# SV601121A.net
KiCad netlist of a schematic drawn in Altium Designer
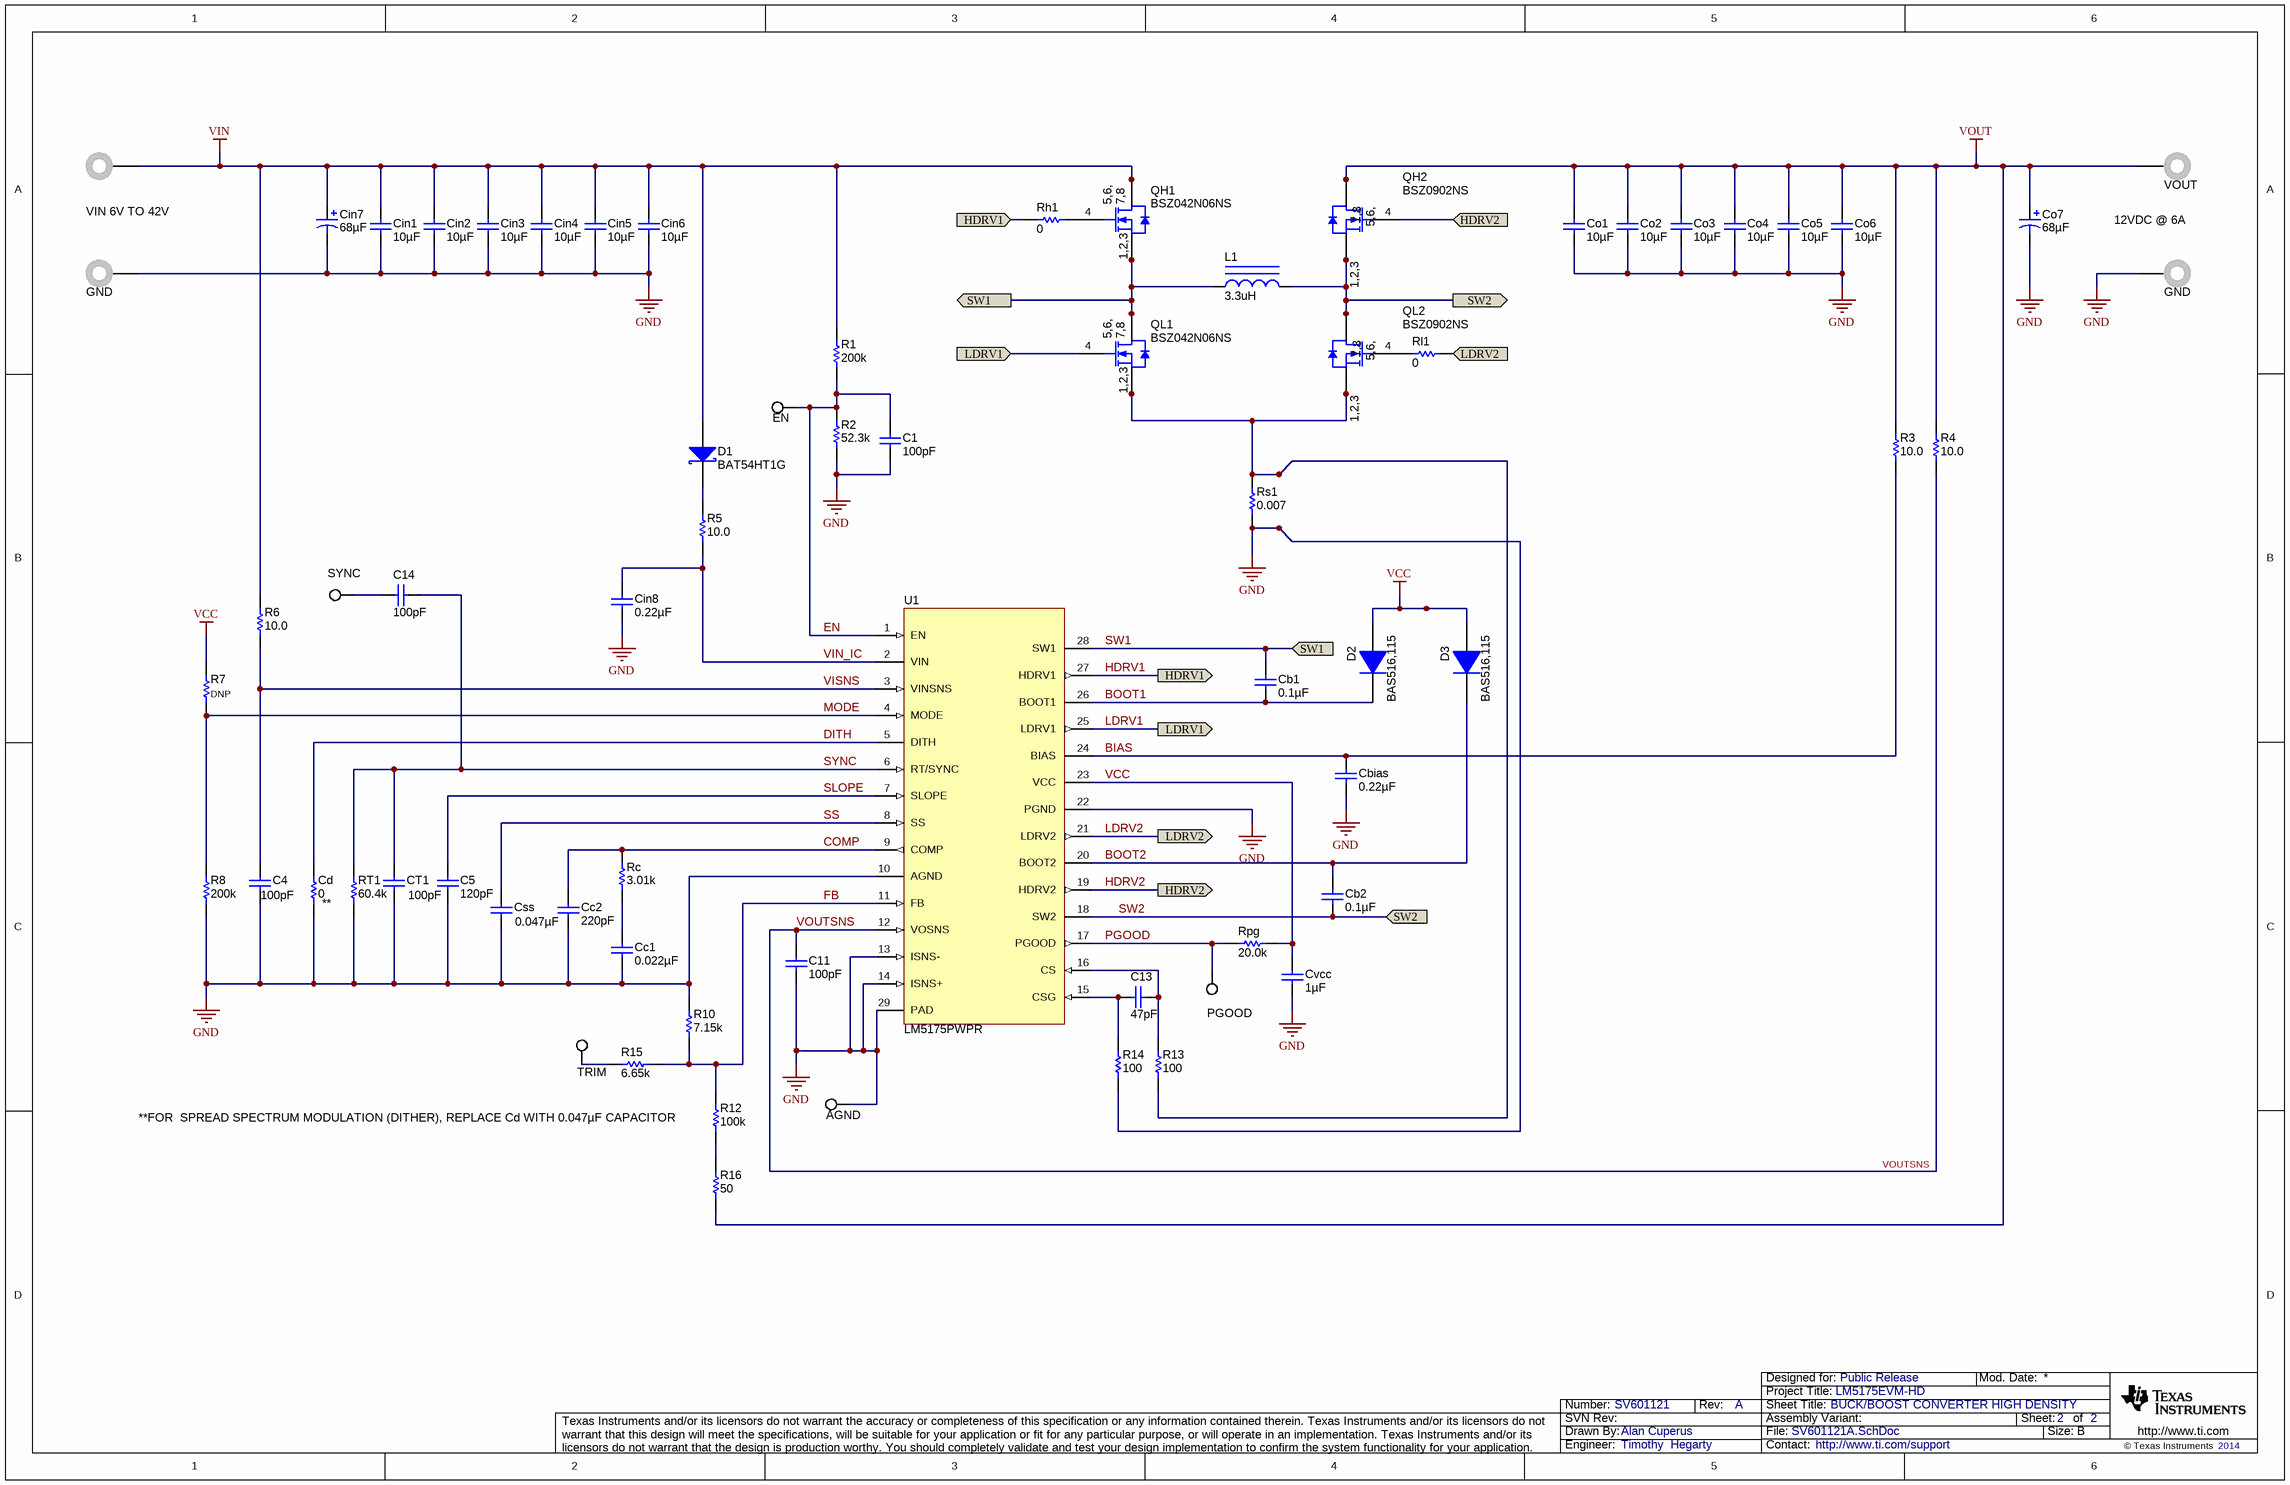
[diagram p0: SV601121A.SchDoc]

(export (version "E")
  (design (tool "Eeschema 10.0.6"))
  (components
    (comp (ref "AGND")
      (value "5015")
      (footprint "Testpoint_Keystone_Miniature")
      (description "Test Point, Miniature, SMT")
      (fields (field (name "MANUFACTURER") "Keystone") (field (name "PUBLISHER") "Texas Instruments"))
      (libsource (lib "Connectors_Keystone") (part "5015"))
    )
    (comp (ref "C1")
      (value "GRM1885C1H101JA01D")
      (footprint "0603L")
      (description "CAP, CERM, 100pF, 50V, +/-5%, C0G/NP0, 0603")
      (fields
        (field (name "VALUEDISPLAYED") "100pF")
        (field (name "MANUFACTURER") "MuRata")
        (field (name "PUBLISHER") "Texas Instruments")
      )
      (libsource (lib "Capacitor_Ceramic") (part "GRM1885C1H101JA01D"))
    )
    (comp (ref "C4")
      (value "GRM1885C1H101JA01D")
      (footprint "0603L")
      (description "CAP, CERM, 100pF, 50V, +/-5%, C0G/NP0, 0603")
      (fields
        (field (name "VALUEDISPLAYED") "100pF")
        (field (name "MANUFACTURER") "MuRata")
        (field (name "PUBLISHER") "Texas Instruments")
      )
      (libsource (lib "Capacitor_Ceramic") (part "GRM1885C1H101JA01D"))
    )
    (comp (ref "C5")
      (value "GRM1885C1H121JA01D")
      (footprint "0603L")
      (description "CAP, CERM, 120pF, 50V, +/-5%, C0G/NP0, 0603")
      (fields
        (field (name "VALUEDISPLAYED") "120pF")
        (field (name "MANUFACTURER") "MuRata")
        (field (name "PUBLISHER") "Texas Instruments")
      )
      (libsource (lib "Capacitor_Ceramic") (part "GRM1885C1H121JA01D"))
    )
    (comp (ref "C11")
      (value "GRM1885C1H101JA01D")
      (footprint "0603L")
      (description "CAP, CERM, 100pF, 50V, +/-5%, C0G/NP0, 0603")
      (fields
        (field (name "VALUEDISPLAYED") "100pF")
        (field (name "MANUFACTURER") "MuRata")
        (field (name "PUBLISHER") "Texas Instruments")
      )
      (libsource (lib "Capacitor_Ceramic") (part "GRM1885C1H101JA01D"))
    )
    (comp (ref "C13")
      (value "GRM1885C1H470JA01D")
      (footprint "0603L")
      (description "CAP, CERM, 47pF, 50V, +/-5%, C0G/NP0, 0603")
      (fields
        (field (name "VALUEDISPLAYED") "47pF")
        (field (name "MANUFACTURER") "MuRata")
        (field (name "PUBLISHER") "Texas Instruments")
      )
      (libsource (lib "Capacitor_Ceramic") (part "GRM1885C1H470JA01D"))
    )
    (comp (ref "C14")
      (value "CGA3E2NP01H101J080AA")
      (footprint "0603L")
      (description "CAP, CERM, 100pF, 50V, +/-5%, C0G/NP0, 0603")
      (fields
        (field (name "VALUEDISPLAYED") "100pF")
        (field (name "MANUFACTURER") "TDK")
        (field (name "PUBLISHER") "Texas Instruments")
      )
      (libsource (lib "Capacitor_Ceramic") (part "CGA3E2NP01H101J080AA"))
    )
    (comp (ref "Cb1")
      (value "GCM188R71H104KA57D")
      (footprint "0603L")
      (description "CAP, CERM, 0.1uF, 50V, +/-10%, X7R, 0603")
      (fields
        (field (name "VALUEDISPLAYED") "0.1µF")
        (field (name "MANUFACTURER") "MuRata")
        (field (name "PUBLISHER") "Texas Instruments")
      )
      (libsource (lib "Capacitor_Ceramic") (part "GCM188R71H104KA57D"))
    )
    (comp (ref "Cb2")
      (value "GCM188R71H104KA57D")
      (footprint "0603L")
      (description "CAP, CERM, 0.1uF, 50V, +/-10%, X7R, 0603")
      (fields
        (field (name "VALUEDISPLAYED") "0.1µF")
        (field (name "MANUFACTURER") "MuRata")
        (field (name "PUBLISHER") "Texas Instruments")
      )
      (libsource (lib "Capacitor_Ceramic") (part "GCM188R71H104KA57D"))
    )
    (comp (ref "Cbias")
      (value "C1608X7R1H224K080AB")
      (footprint "0603_HV")
      (description "CAP, CERM, 0.22uF, 50V, +/-10%, X7R, 0603")
      (fields
        (field (name "VALUEDISPLAYED") "0.22µF")
        (field (name "MANUFACTURER") "TDK")
        (field (name "PUBLISHER") "Texas Instruments")
      )
      (libsource (lib "Capacitor_Ceramic") (part "C1608X7R1H224K080AB"))
    )
    (comp (ref "Cc1")
      (value "GRM188R71H223KA01D")
      (footprint "0603L")
      (description "CAP, CERM, 0.022 µF, 50 V, +/- 10%, X7R, 0603")
      (fields
        (field (name "VALUEDISPLAYED") "0.022µF")
        (field (name "MANUFACTURER") "MuRata")
        (field (name "PUBLISHER") "Texas Instruments")
      )
      (libsource (lib "Capacitor_Ceramic") (part "GRM188R71H223KA01D"))
    )
    (comp (ref "Cc2")
      (value "GRM1885C1H221JA01D")
      (footprint "0603L")
      (description "CAP, CERM, 220 pF, 50 V, +/- 5%, C0G/NP0, 0603")
      (fields
        (field (name "VALUEDISPLAYED") "220pF")
        (field (name "MANUFACTURER") "MuRata")
        (field (name "PUBLISHER") "Texas Instruments")
      )
      (libsource (lib "Capacitor_Ceramic") (part "GRM1885C1H221JA01D"))
    )
    (comp (ref "Cd")
      (value "RC0603JR-070RL")
      (footprint "0603L")
      (description "RES, 0, 5%, 0.1 W, 0603")
      (fields
        (field (name "MANUFACTURER") "Yageo America")
        (field (name "VALUEDISPLAYED") "0")
        (field (name "PUBLISHER") "Texas Instruments")
      )
      (libsource (lib "Resistor_0603") (part "RC0603JR-070RL"))
    )
    (comp (ref "Cin1")
      (value "GRM32ER71H106KA12L")
      (footprint "1210L")
      (description "CAP, CERM, 10uF, 50V, +/-10%, X7R, 1210")
      (fields
        (field (name "VALUEDISPLAYED") "10µF")
        (field (name "MANUFACTURER") "MuRata")
        (field (name "PUBLISHER") "Texas Instruments")
      )
      (libsource (lib "Capacitor_Ceramic") (part "GRM32ER71H106KA12L"))
    )
    (comp (ref "Cin2")
      (value "GRM32ER71H106KA12L")
      (footprint "1210L")
      (description "CAP, CERM, 10uF, 50V, +/-10%, X7R, 1210")
      (fields
        (field (name "VALUEDISPLAYED") "10µF")
        (field (name "MANUFACTURER") "MuRata")
        (field (name "PUBLISHER") "Texas Instruments")
      )
      (libsource (lib "Capacitor_Ceramic") (part "GRM32ER71H106KA12L"))
    )
    (comp (ref "Cin3")
      (value "GRM32ER71H106KA12L")
      (footprint "1210L")
      (description "CAP, CERM, 10uF, 50V, +/-10%, X7R, 1210")
      (fields
        (field (name "VALUEDISPLAYED") "10µF")
        (field (name "MANUFACTURER") "MuRata")
        (field (name "PUBLISHER") "Texas Instruments")
      )
      (libsource (lib "Capacitor_Ceramic") (part "GRM32ER71H106KA12L"))
    )
    (comp (ref "Cin4")
      (value "GRM32ER71H106KA12L")
      (footprint "1210L")
      (description "CAP, CERM, 10uF, 50V, +/-10%, X7R, 1210")
      (fields
        (field (name "VALUEDISPLAYED") "10µF")
        (field (name "MANUFACTURER") "MuRata")
        (field (name "PUBLISHER") "Texas Instruments")
      )
      (libsource (lib "Capacitor_Ceramic") (part "GRM32ER71H106KA12L"))
    )
    (comp (ref "Cin5")
      (value "GRM32ER71H106KA12L")
      (footprint "1210L")
      (description "CAP, CERM, 10uF, 50V, +/-10%, X7R, 1210")
      (fields
        (field (name "VALUEDISPLAYED") "10µF")
        (field (name "MANUFACTURER") "MuRata")
        (field (name "PUBLISHER") "Texas Instruments")
      )
      (libsource (lib "Capacitor_Ceramic") (part "GRM32ER71H106KA12L"))
    )
    (comp (ref "Cin6")
      (value "GRM32ER71H106KA12L")
      (footprint "1210L")
      (description "CAP, CERM, 10uF, 50V, +/-10%, X7R, 1210")
      (fields
        (field (name "VALUEDISPLAYED") "10µF")
        (field (name "MANUFACTURER") "MuRata")
        (field (name "PUBLISHER") "Texas Instruments")
      )
      (libsource (lib "Capacitor_Ceramic") (part "GRM32ER71H106KA12L"))
    )
    (comp (ref "Cin7")
      (value "EEHZC1H680P")
      (footprint "SM_RADIAL_8MM")
      (description "CAP, AL, 68 µF, 50 V, +/- 20%, 30 ohm, SMD")
      (fields
        (field (name "VALUEDISPLAYED") "68µF")
        (field (name "MANUFACTURER") "Panasonic")
        (field (name "PUBLISHER") "Texas Instruments")
      )
      (libsource (lib "Capacitor_Aluminum") (part "EEHZC1H680P"))
    )
    (comp (ref "Cin8")
      (value "C1608X7R1H224K080AB")
      (footprint "0603_HV")
      (description "CAP, CERM, 0.22uF, 50V, +/-10%, X7R, 0603")
      (fields
        (field (name "VALUEDISPLAYED") "0.22µF")
        (field (name "MANUFACTURER") "TDK")
        (field (name "PUBLISHER") "Texas Instruments")
      )
      (libsource (lib "Capacitor_Ceramic") (part "C1608X7R1H224K080AB"))
    )
    (comp (ref "Co1")
      (value "GRM32ER71H106KA12L")
      (footprint "1210L")
      (description "CAP, CERM, 10 µF, 50 V, +/- 10%, X7R, 1210")
      (fields
        (field (name "VALUEDISPLAYED") "10µF")
        (field (name "MANUFACTURER") "MuRata")
        (field (name "PUBLISHER") "Texas Instruments")
      )
      (libsource (lib "Capacitor_Ceramic") (part "GRM32ER71H106KA12L"))
    )
    (comp (ref "Co2")
      (value "GRM32ER71H106KA12L")
      (footprint "1210L")
      (description "CAP, CERM, 10 µF, 50 V, +/- 10%, X7R, 1210")
      (fields
        (field (name "VALUEDISPLAYED") "10µF")
        (field (name "MANUFACTURER") "MuRata")
        (field (name "PUBLISHER") "Texas Instruments")
      )
      (libsource (lib "Capacitor_Ceramic") (part "GRM32ER71H106KA12L"))
    )
    (comp (ref "Co3")
      (value "GRM32ER71H106KA12L")
      (footprint "1210L")
      (description "CAP, CERM, 10 µF, 50 V, +/- 10%, X7R, 1210")
      (fields
        (field (name "VALUEDISPLAYED") "10µF")
        (field (name "MANUFACTURER") "MuRata")
        (field (name "PUBLISHER") "Texas Instruments")
      )
      (libsource (lib "Capacitor_Ceramic") (part "GRM32ER71H106KA12L"))
    )
    (comp (ref "Co4")
      (value "GRM32ER71H106KA12L")
      (footprint "1210L")
      (description "CAP, CERM, 10 µF, 50 V, +/- 10%, X7R, 1210")
      (fields
        (field (name "VALUEDISPLAYED") "10µF")
        (field (name "MANUFACTURER") "MuRata")
        (field (name "PUBLISHER") "Texas Instruments")
      )
      (libsource (lib "Capacitor_Ceramic") (part "GRM32ER71H106KA12L"))
    )
    (comp (ref "Co5")
      (value "GRM32ER71H106KA12L")
      (footprint "1210L")
      (description "CAP, CERM, 10 µF, 50 V, +/- 10%, X7R, 1210")
      (fields
        (field (name "VALUEDISPLAYED") "10µF")
        (field (name "MANUFACTURER") "MuRata")
        (field (name "PUBLISHER") "Texas Instruments")
      )
      (libsource (lib "Capacitor_Ceramic") (part "GRM32ER71H106KA12L"))
    )
    (comp (ref "Co6")
      (value "GRM32ER71H106KA12L")
      (footprint "1210L")
      (description "CAP, CERM, 10 µF, 50 V, +/- 10%, X7R, 1210")
      (fields
        (field (name "VALUEDISPLAYED") "10µF")
        (field (name "MANUFACTURER") "MuRata")
        (field (name "PUBLISHER") "Texas Instruments")
      )
      (libsource (lib "Capacitor_Ceramic") (part "GRM32ER71H106KA12L"))
    )
    (comp (ref "Co7")
      (value "EEHZC1H680P")
      (footprint "SM_RADIAL_8MM")
      (description "CAP, AL, 68 µF, 50 V, +/- 20%, 30 ohm, SMD")
      (fields
        (field (name "VALUEDISPLAYED") "68µF")
        (field (name "MANUFACTURER") "Panasonic")
        (field (name "PUBLISHER") "Texas Instruments")
      )
      (libsource (lib "Capacitor_Aluminum") (part "EEHZC1H680P"))
    )
    (comp (ref "Css")
      (value "GRM188R71H473KA61D")
      (footprint "0603L")
      (description "CAP, CERM, 0.047 µF, 50 V, +/- 10%, X7R, 0603")
      (fields
        (field (name "VALUEDISPLAYED") "0.047µF")
        (field (name "MANUFACTURER") "MuRata")
        (field (name "PUBLISHER") "Texas Instruments")
      )
      (libsource (lib "Capacitor_Ceramic") (part "GRM188R71H473KA61D"))
    )
    (comp (ref "CT1")
      (value "DNP")
      (footprint "0603L")
      (description "CAP, CERM, 100pF, 50V, +/-5%, C0G/NP0, 0603")
      (fields
        (field (name "PARTNUMBER") "GRM1885C1H101JA01D")
        (field (name "VALUEDISPLAYED") "100pF")
        (field (name "MANUFACTURER") "MuRata")
        (field (name "PUBLISHER") "Texas Instruments")
      )
      (libsource (lib "Capacitor_Ceramic") (part "GRM1885C1H101JA01D"))
    )
    (comp (ref "Cvcc")
      (value "GRM188R71C105KA12D")
      (footprint "0603L")
      (description "CAP, CERM, 1uF, 16V, +/-10%, X7R, 0603")
      (fields
        (field (name "VALUEDISPLAYED") "1µF")
        (field (name "MANUFACTURER") "MuRata")
        (field (name "PUBLISHER") "Texas Instruments")
      )
      (libsource (lib "Capacitor_Ceramic") (part "GRM188R71C105KA12D"))
    )
    (comp (ref "D1")
      (value "BAT54HT1G")
      (footprint "sod-323")
      (description "Diode, Schottky, 30V, 0.2A, SOD-323")
      (fields (field (name "MANUFACTURER") "ON Semiconductor") (field (name "PUBLISHER") "Texas Instruments"))
      (libsource (lib "Diode") (part "BAT54HT1G"))
    )
    (comp (ref "D2")
      (value "BAS516,115")
      (footprint "SOD-523")
      (description "Diode, Switching, 100V, 0.25A, SOD-523")
      (fields
        (field (name "MANUFACTURER") "NXP Semiconductor")
        (field (name "PUBLISHER") "Texas Instruments")
      )
      (libsource (lib "Diode") (part "BAS516,115"))
    )
    (comp (ref "D3")
      (value "BAS516,115")
      (footprint "SOD-523")
      (description "Diode, Switching, 100V, 0.25A, SOD-523")
      (fields
        (field (name "MANUFACTURER") "NXP Semiconductor")
        (field (name "PUBLISHER") "Texas Instruments")
      )
      (libsource (lib "Diode") (part "BAS516,115"))
    )
    (comp (ref "EN")
      (value "5015")
      (footprint "Testpoint_Keystone_Miniature")
      (description "Test Point, Miniature, SMT")
      (fields (field (name "MANUFACTURER") "Keystone") (field (name "PUBLISHER") "Texas Instruments"))
      (libsource (lib "Connectors_Keystone") (part "5015"))
    )
    (comp (ref "J1")
      (value "VIN 6V TO 42V")
      (footprint "Johnson_108-0740-001")
      (description "Standard Banana Jack, Uninsulated, 15A")
      (fields
        (field (name "PARTNUMBER") "108-0740-001")
        (field (name "MANUFACTURER") "Emerson Network Power")
        (field (name "SYMBOLCREATOR") "a0412235")
        (field (name "PUBLISHER") "Texas Instruments")
      )
      (libsource (lib "Connectors_Other") (part "108-0740-001"))
    )
    (comp (ref "J2")
      (value "VOUT")
      (footprint "Johnson_108-0740-001")
      (description "Standard Banana Jack, Uninsulated, 15A")
      (fields
        (field (name "PARTNUMBER") "108-0740-001")
        (field (name "MANUFACTURER") "Emerson Network Power")
        (field (name "SYMBOLCREATOR") "a0412235")
        (field (name "PUBLISHER") "Texas Instruments")
      )
      (libsource (lib "Connectors_Other") (part "108-0740-001"))
    )
    (comp (ref "J3")
      (value "GND")
      (footprint "Johnson_108-0740-001")
      (description "Standard Banana Jack, Uninsulated, 15A")
      (fields
        (field (name "PARTNUMBER") "108-0740-001")
        (field (name "MANUFACTURER") "Emerson Network Power")
        (field (name "SYMBOLCREATOR") "a0412235")
        (field (name "PUBLISHER") "Texas Instruments")
      )
      (libsource (lib "Connectors_Other") (part "108-0740-001"))
    )
    (comp (ref "J4")
      (value "GND")
      (footprint "Johnson_108-0740-001")
      (description "Standard Banana Jack, Uninsulated, 15A")
      (fields
        (field (name "PARTNUMBER") "108-0740-001")
        (field (name "MANUFACTURER") "Emerson Network Power")
        (field (name "SYMBOLCREATOR") "a0412235")
        (field (name "PUBLISHER") "Texas Instruments")
      )
      (libsource (lib "Connectors_Other") (part "108-0740-001"))
    )
    (comp (ref "L1")
      (value "3.3uH")
      (footprint "PIMB135T")
      (description "Inductor, Drum Core, Powdered Iron, 3.3uH, 14A, 0.007 ohm, SMD")
      (fields
        (field (name "PARTNUMBER") "PIMB135T-3R3MS")
        (field (name "MANUFACTURER") "Cyntec")
        (field (name "PUBLISHER") "Texas Instruments")
      )
      (libsource (lib "Inductor_Other") (part "PIMB135T-3R3MS"))
    )
    (comp (ref "PGOOD")
      (value "5015")
      (footprint "Testpoint_Keystone_Miniature")
      (description "Test Point, Miniature, SMT")
      (fields (field (name "MANUFACTURER") "Keystone") (field (name "PUBLISHER") "Texas Instruments"))
      (libsource (lib "Connectors_Keystone") (part "5015"))
    )
    (comp (ref "QH1")
      (value "BSZ042N06NS")
      (footprint "FETS:PG-TSDSON-8")
      (description "MOSFET N-CH 60V 19A 8TSDSON")
      (fields (field (name "MANUFACTURER") "Infineon Technologies") (field (name "SYMBOLCREATOR") "Use a-id"))
      (libsource (lib "FETs") (part "BSZ042N06NS"))
    )
    (comp (ref "QH2")
      (value "BSZ0902NS")
      (footprint "PG-TSDSON-8")
      (description "MOSFET, N-CH, 30V, 40A, PG-TSDSON-8")
      (fields
        (field (name "MANUFACTURER") "Infineon Technologies")
        (field (name "PUBLISHER") "Texas Instruments")
      )
      (libsource (lib "FETs") (part "BSZ0902NS"))
    )
    (comp (ref "QL1")
      (value "BSZ042N06NS")
      (footprint "FETS:PG-TSDSON-8")
      (description "MOSFET N-CH 60V 19A 8TSDSON")
      (fields (field (name "MANUFACTURER") "Infineon Technologies") (field (name "SYMBOLCREATOR") "Use a-id"))
      (libsource (lib "FETs") (part "BSZ042N06NS"))
    )
    (comp (ref "QL2")
      (value "BSZ0902NS")
      (footprint "PG-TSDSON-8")
      (description "MOSFET, N-CH, 30V, 40A, PG-TSDSON-8")
      (fields
        (field (name "MANUFACTURER") "Infineon Technologies")
        (field (name "PUBLISHER") "Texas Instruments")
      )
      (libsource (lib "FETs") (part "BSZ0902NS"))
    )
    (comp (ref "R1")
      (value "200k")
      (footprint "0603_HV")
      (description "RES, 200k ohm, 1%, 0.1W, 0603")
      (fields
        (field (name "PARTNUMBER") "RC0603FR-07200KL")
        (field (name "MANUFACTURER") "Yageo America")
        (field (name "PUBLISHER") "Texas Instruments")
      )
      (libsource (lib "Resistor_0603") (part "RC0603FR-07200KL"))
    )
    (comp (ref "R2")
      (value "RC0603FR-0752K3L")
      (footprint "0603_HV")
      (description "RES, 52.3 k, 1%, 0.1 W, 0603")
      (fields
        (field (name "MANUFACTURER") "Yageo America")
        (field (name "VALUEDISPLAYED") "52.3k")
        (field (name "PUBLISHER") "Texas Instruments")
      )
      (libsource (lib "Resistor_0603") (part "RC0603FR-0752K3L"))
    )
    (comp (ref "R3")
      (value "10.0")
      (footprint "0603_HV")
      (description "RES, 10.0 ohm, 1%, 0.1W, 0603")
      (fields
        (field (name "PARTNUMBER") "RC0603FR-0710RL")
        (field (name "MANUFACTURER") "Yageo America")
        (field (name "PUBLISHER") "Texas Instruments")
      )
      (libsource (lib "Resistor_0603") (part "RC0603FR-0710RL"))
    )
    (comp (ref "R4")
      (value "CRCW060310R0FKEA")
      (footprint "0603L")
      (description "RES, 10.0, 1%, 0.1 W, 0603")
      (fields
        (field (name "MANUFACTURER") "Vishay-Dale")
        (field (name "VALUEDISPLAYED") "10.0")
        (field (name "PUBLISHER") "Texas Instruments")
      )
      (libsource (lib "Resistor_0603") (part "CRCW060310R0FKEA"))
    )
    (comp (ref "R5")
      (value "10.0")
      (footprint "0603L")
      (description "RES, 10.0 ohm, 1%, 0.1W, 0603")
      (fields
        (field (name "PARTNUMBER") "RC0603FR-0710RL")
        (field (name "MANUFACTURER") "Yageo America")
        (field (name "PUBLISHER") "Texas Instruments")
      )
      (libsource (lib "Resistor_0603") (part "RC0603FR-0710RL"))
    )
    (comp (ref "R6")
      (value "10.0")
      (footprint "0603L")
      (description "RES, 10.0 ohm, 1%, 0.1W, 0603")
      (fields
        (field (name "PARTNUMBER") "RC0603FR-0710RL")
        (field (name "MANUFACTURER") "Yageo America")
        (field (name "PUBLISHER") "Texas Instruments")
      )
      (libsource (lib "Resistor_0603") (part "RC0603FR-0710RL"))
    )
    (comp (ref "R7")
      (value "DNP")
      (footprint "0603L")
      (description "RES, 0 ohm, 5%, 0.1W, 0603")
      (fields
        (field (name "PARTNUMBER") "CRCW06030000Z0EA")
        (field (name "MANUFACTURER") "Vishay-Dale")
        (field (name "PUBLISHER") "Texas Instruments")
      )
      (libsource (lib "Resistor_0603") (part "CRCW06030000Z0EA"))
    )
    (comp (ref "R8")
      (value "CRCW0603200KFKEA")
      (footprint "0603L")
      (description "RES, 200 k, 1%, 0.1 W, 0603")
      (fields
        (field (name "MANUFACTURER") "Vishay-Dale")
        (field (name "VALUEDISPLAYED") "200k")
        (field (name "PUBLISHER") "Texas Instruments")
      )
      (libsource (lib "Resistor_0603") (part "CRCW0603200KFKEA"))
    )
    (comp (ref "R10")
      (value "7.15k")
      (footprint "0603L")
      (description "RES, 7.15k ohm, 1%, 0.1W, 0603")
      (fields
        (field (name "PARTNUMBER") "RC0603FR-077K15L")
        (field (name "MANUFACTURER") "Yageo America")
        (field (name "PUBLISHER") "Texas Instruments")
      )
      (libsource (lib "Resistor_0603") (part "RC0603FR-077K15L"))
    )
    (comp (ref "R12")
      (value "100k")
      (footprint "0603L")
      (description "RES, 100k ohm, 1%, 0.1W, 0603")
      (fields
        (field (name "PARTNUMBER") "RC0603FR-07100KL")
        (field (name "MANUFACTURER") "Yageo America")
        (field (name "PUBLISHER") "Texas Instruments")
      )
      (libsource (lib "Resistor_0603") (part "RC0603FR-07100KL"))
    )
    (comp (ref "R13")
      (value "100")
      (footprint "0603L")
      (description "RES, 100 ohm, 1%, 0.1W, 0603")
      (fields
        (field (name "PARTNUMBER") "RC0603FR-07100RL")
        (field (name "MANUFACTURER") "Yageo America")
        (field (name "PUBLISHER") "Texas Instruments")
      )
      (libsource (lib "Resistor_0603") (part "RC0603FR-07100RL"))
    )
    (comp (ref "R14")
      (value "100")
      (footprint "0603L")
      (description "RES, 100 ohm, 1%, 0.1W, 0603")
      (fields
        (field (name "PARTNUMBER") "RC0603FR-07100RL")
        (field (name "MANUFACTURER") "Yageo America")
        (field (name "PUBLISHER") "Texas Instruments")
      )
      (libsource (lib "Resistor_0603") (part "RC0603FR-07100RL"))
    )
    (comp (ref "R15")
      (value "RC0603FR-076K65L")
      (footprint "0603L")
      (description "RES, 6.65 k, 1%, 0.1 W, 0603")
      (fields
        (field (name "MANUFACTURER") "Yageo America")
        (field (name "VALUEDISPLAYED") "6.65k")
        (field (name "PUBLISHER") "Texas Instruments")
      )
      (libsource (lib "Resistor_0603") (part "RC0603FR-076K65L"))
    )
    (comp (ref "R16")
      (value "CRCW060350R0FKEA")
      (footprint "0603L")
      (description "RES, 50, 1%, 0.1 W, 0603")
      (fields
        (field (name "MANUFACTURER") "Vishay-Dale")
        (field (name "VALUEDISPLAYED") "50")
        (field (name "PUBLISHER") "Texas Instruments")
      )
      (libsource (lib "Resistor_0603") (part "CRCW060350R0FKEA"))
    )
    (comp (ref "Rc")
      (value "3.01k")
      (footprint "0603L")
      (description "RES, 3.01k ohm, 1%, 0.1W, 0603")
      (fields
        (field (name "PARTNUMBER") "RC0603FR-073K01L")
        (field (name "MANUFACTURER") "Yageo America")
        (field (name "PUBLISHER") "Texas Instruments")
      )
      (libsource (lib "Resistor_0603") (part "RC0603FR-073K01L"))
    )
    (comp (ref "Rh1")
      (value "0")
      (footprint "0603L")
      (description "RES, 0 ohm, 5%, 0.1W, 0603")
      (fields
        (field (name "PARTNUMBER") "CRCW06030000Z0EA")
        (field (name "MANUFACTURER") "Vishay-Dale")
        (field (name "PUBLISHER") "Texas Instruments")
      )
      (libsource (lib "Resistor_0603") (part "CRCW06030000Z0EA"))
    )
    (comp (ref "Rl1")
      (value "0")
      (footprint "0603L")
      (description "RES, 0 ohm, 5%, 0.1W, 0603")
      (fields
        (field (name "PARTNUMBER") "CRCW06030000Z0EA")
        (field (name "MANUFACTURER") "Vishay-Dale")
        (field (name "PUBLISHER") "Texas Instruments")
      )
      (libsource (lib "Resistor_0603") (part "CRCW06030000Z0EA"))
    )
    (comp (ref "Rpg")
      (value "RC0603FR-0720KL")
      (footprint "0603L")
      (description "RES, 20.0 k, 1%, 0.1 W, 0603")
      (fields
        (field (name "MANUFACTURER") "Yageo America")
        (field (name "VALUEDISPLAYED") "20.0k")
        (field (name "PUBLISHER") "Texas Instruments")
      )
      (libsource (lib "Resistor_0603") (part "RC0603FR-0720KL"))
    )
    (comp (ref "Rs1")
      (value "0.007")
      (footprint "Resistor_OtherSMT:2512_WIDE")
      (description "RES 0.007 OHM 3W 1% 2512 WIDE")
      (fields
        (field (name "PARTNUMBER") "KRL6432E-M-R007-F-T1")
        (field (name "MANUFACTURER") "Susumu")
        (field (name "SYMBOLCREATOR") "Use a-id")
      )
      (libsource (lib "Resistor_OtherSMT") (part "KRL6432E-M-R007-F-T1"))
    )
    (comp (ref "RT1")
      (value "RC0603FR-0760K4L")
      (footprint "0603L")
      (description "RES, 60.4 k, 1%, 0.1 W, 0603")
      (fields
        (field (name "MANUFACTURER") "Yageo America")
        (field (name "VALUEDISPLAYED") "60.4k")
        (field (name "PUBLISHER") "Texas Instruments")
      )
      (libsource (lib "Resistor_0603") (part "RC0603FR-0760K4L"))
    )
    (comp (ref "SYNC")
      (value "5015")
      (footprint "Testpoint_Keystone_Miniature")
      (description "Test Point, Miniature, SMT")
      (fields (field (name "MANUFACTURER") "Keystone") (field (name "PUBLISHER") "Texas Instruments"))
      (libsource (lib "Connectors_Keystone") (part "5015"))
    )
    (comp (ref "TRIM")
      (value "5015")
      (footprint "Testpoint_Keystone_Miniature")
      (description "Test Point, Miniature, SMT")
      (fields (field (name "MANUFACTURER") "Keystone") (field (name "PUBLISHER") "Texas Instruments"))
      (libsource (lib "Connectors_Keystone") (part "5015"))
    )
    (comp (ref "U1")
      (value "LM5175PWPR")
      (footprint "PWP0028F_N")
      (description "42V Wide VIN 4-Switch Synchronous Buck-Boost Controller, PWP0028F")
      (fields
        (field (name "ALTERNATE PARTNUMBER") "LM5175PWPT")
        (field (name "MANUFACTURER") "Texas Instruments")
        (field (name "SYMBOLCREATOR") "a0411947")
        (field (name "PUBLISHER") "Texas Instruments")
      )
      (libsource (lib "TI_Pre_RTM") (part "LM5175PWPR"))
    )
  )
  (nets
    (net (code "1") (name "/BIAS") (class "Default")
      (node (ref "Cbias") (pin "1") (pinfunction "1_1") (pintype "passive"))
      (node (ref "R3") (pin "1") (pinfunction "1_1") (pintype "passive"))
      (node (ref "U1") (pin "24") (pinfunction "BIAS_24") (pintype "power_in"))
    )
    (net (code "2") (name "/BOOT1") (class "Default")
      (node (ref "Cb1") (pin "1") (pinfunction "1_1") (pintype "passive"))
      (node (ref "D2") (pin "1") (pinfunction "K_1") (pintype "passive"))
      (node (ref "U1") (pin "26") (pinfunction "BOOT1_26") (pintype "power_in"))
    )
    (net (code "3") (name "/BOOT2") (class "Default")
      (node (ref "Cb2") (pin "2") (pinfunction "2_2") (pintype "passive"))
      (node (ref "D3") (pin "1") (pinfunction "K_1") (pintype "passive"))
      (node (ref "U1") (pin "20") (pinfunction "BOOT2_20") (pintype "power_in"))
    )
    (net (code "4") (name "/COMP") (class "Default")
      (node (ref "Cc2") (pin "2") (pinfunction "2_2") (pintype "passive"))
      (node (ref "Rc") (pin "2") (pinfunction "2_2") (pintype "passive"))
      (node (ref "U1") (pin "9") (pinfunction "COMP_9") (pintype "output"))
    )
    (net (code "5") (name "/DITH") (class "Default")
      (node (ref "Cd") (pin "2") (pinfunction "2_2") (pintype "passive"))
      (node (ref "U1") (pin "5") (pinfunction "DITH_5") (pintype "passive"))
    )
    (net (code "6") (name "/EN") (class "Default")
      (node (ref "C1") (pin "2") (pinfunction "2_2") (pintype "passive"))
      (node (ref "EN") (pin "1") (pintype "passive"))
      (node (ref "R1") (pin "1") (pinfunction "1_1") (pintype "passive"))
      (node (ref "R2") (pin "2") (pinfunction "2_2") (pintype "passive"))
      (node (ref "U1") (pin "1") (pinfunction "EN_1") (pintype "input"))
    )
    (net (code "7") (name "/FB") (class "Default")
      (node (ref "R10") (pin "1") (pinfunction "1_1") (pintype "passive"))
      (node (ref "R12") (pin "2") (pinfunction "2_2") (pintype "passive"))
      (node (ref "R15") (pin "2") (pinfunction "2_2") (pintype "passive"))
      (node (ref "U1") (pin "11") (pinfunction "FB_11") (pintype "input"))
    )
    (net (code "8") (name "/HDRV1") (class "Default")
      (node (ref "Rh1") (pin "1") (pinfunction "1_1") (pintype "passive"))
      (node (ref "U1") (pin "27") (pinfunction "HDRV1_27") (pintype "output"))
    )
    (net (code "9") (name "/HDRV2") (class "Default")
      (node (ref "QH2") (pin "4") (pinfunction "G_4") (pintype "passive"))
      (node (ref "U1") (pin "19") (pinfunction "HDRV2_19") (pintype "output"))
    )
    (net (code "10") (name "/LDRV1") (class "Default")
      (node (ref "QL1") (pin "4") (pinfunction "G_4") (pintype "passive"))
      (node (ref "U1") (pin "25") (pinfunction "LDRV1_25") (pintype "output"))
    )
    (net (code "11") (name "/LDRV2") (class "Default")
      (node (ref "Rl1") (pin "2") (pinfunction "2_2") (pintype "passive"))
      (node (ref "U1") (pin "21") (pinfunction "LDRV2_21") (pintype "output"))
    )
    (net (code "12") (name "/MODE") (class "Default")
      (node (ref "R7") (pin "1") (pinfunction "1_1") (pintype "passive"))
      (node (ref "R8") (pin "2") (pinfunction "2_2") (pintype "passive"))
      (node (ref "U1") (pin "4") (pinfunction "MODE_4") (pintype "input"))
    )
    (net (code "13") (name "/PGOOD") (class "Default")
      (node (ref "PGOOD") (pin "1") (pintype "passive"))
      (node (ref "Rpg") (pin "2") (pinfunction "2_2") (pintype "passive"))
      (node (ref "U1") (pin "17") (pinfunction "PGOOD_17") (pintype "output"))
    )
    (net (code "14") (name "/SLOPE") (class "Default")
      (node (ref "C5") (pin "1") (pinfunction "1_1") (pintype "passive"))
      (node (ref "U1") (pin "7") (pinfunction "SLOPE_7") (pintype "input"))
    )
    (net (code "15") (name "/SS") (class "Default")
      (node (ref "Css") (pin "1") (pinfunction "1_1") (pintype "passive"))
      (node (ref "U1") (pin "8") (pinfunction "SS_8") (pintype "input"))
    )
    (net (code "16") (name "/SW1") (class "Default")
      (node (ref "Cb1") (pin "2") (pinfunction "2_2") (pintype "passive"))
      (node (ref "L1") (pin "1") (pinfunction "1_1") (pintype "passive"))
      (node (ref "QH1") (pin "1") (pinfunction "S_1") (pintype "passive"))
      (node (ref "QH1") (pin "2") (pinfunction "S_2") (pintype "passive"))
      (node (ref "QH1") (pin "3") (pinfunction "S_3") (pintype "passive"))
      (node (ref "QL1") (pin "5") (pinfunction "D_5") (pintype "passive"))
      (node (ref "QL1") (pin "6") (pinfunction "D_6") (pintype "passive"))
      (node (ref "QL1") (pin "7") (pinfunction "D_7") (pintype "passive"))
      (node (ref "QL1") (pin "8") (pinfunction "D_8") (pintype "passive"))
      (node (ref "QL1") (pin "9") (pinfunction "D_9") (pintype "passive"))
      (node (ref "U1") (pin "28") (pinfunction "SW1_28") (pintype "power_in"))
    )
    (net (code "17") (name "/SW2") (class "Default")
      (node (ref "Cb2") (pin "1") (pinfunction "1_1") (pintype "passive"))
      (node (ref "L1") (pin "2") (pinfunction "2_2") (pintype "passive"))
      (node (ref "QH2") (pin "1") (pinfunction "S_1") (pintype "passive"))
      (node (ref "QH2") (pin "2") (pinfunction "S_2") (pintype "passive"))
      (node (ref "QH2") (pin "3") (pinfunction "S_3") (pintype "passive"))
      (node (ref "QL2") (pin "5") (pinfunction "D_5") (pintype "passive"))
      (node (ref "QL2") (pin "6") (pinfunction "D_6") (pintype "passive"))
      (node (ref "QL2") (pin "7") (pinfunction "D_7") (pintype "passive"))
      (node (ref "QL2") (pin "8") (pinfunction "D_8") (pintype "passive"))
      (node (ref "QL2") (pin "9") (pinfunction "D_9") (pintype "passive"))
      (node (ref "U1") (pin "18") (pinfunction "SW2_18") (pintype "power_in"))
    )
    (net (code "18") (name "/SYNC") (class "Default")
      (node (ref "C14") (pin "1") (pinfunction "1_1") (pintype "passive"))
      (node (ref "CT1") (pin "2") (pinfunction "2_2") (pintype "passive"))
      (node (ref "RT1") (pin "2") (pinfunction "2_2") (pintype "passive"))
      (node (ref "U1") (pin "6") (pinfunction "RT/SYNC_6") (pintype "input"))
    )
    (net (code "19") (name "/VIN_IC") (class "Default")
      (node (ref "Cin8") (pin "1") (pinfunction "1_1") (pintype "passive"))
      (node (ref "R5") (pin "1") (pinfunction "1_1") (pintype "passive"))
      (node (ref "U1") (pin "2") (pinfunction "VIN_2") (pintype "power_in"))
    )
    (net (code "20") (name "/VISNS") (class "Default")
      (node (ref "C4") (pin "2") (pinfunction "2_2") (pintype "passive"))
      (node (ref "R6") (pin "2") (pinfunction "2_2") (pintype "passive"))
      (node (ref "U1") (pin "3") (pinfunction "VINSNS_3") (pintype "input"))
    )
    (net (code "21") (name "/VOUTSNS") (class "Default")
      (node (ref "C11") (pin "1") (pinfunction "1_1") (pintype "passive"))
      (node (ref "R4") (pin "1") (pinfunction "1_1") (pintype "passive"))
      (node (ref "U1") (pin "12") (pinfunction "VOSNS_12") (pintype "input"))
    )
    (net (code "22") (name "GND") (class "Default")
      (node (ref "AGND") (pin "1") (pintype "passive"))
      (node (ref "C1") (pin "1") (pinfunction "1_1") (pintype "passive"))
      (node (ref "C11") (pin "2") (pinfunction "2_2") (pintype "passive"))
      (node (ref "C4") (pin "1") (pinfunction "1_1") (pintype "passive"))
      (node (ref "C5") (pin "2") (pinfunction "2_2") (pintype "passive"))
      (node (ref "CT1") (pin "1") (pinfunction "1_1") (pintype "passive"))
      (node (ref "Cbias") (pin "2") (pinfunction "2_2") (pintype "passive"))
      (node (ref "Cc1") (pin "2") (pinfunction "2_2") (pintype "passive"))
      (node (ref "Cc2") (pin "1") (pinfunction "1_1") (pintype "passive"))
      (node (ref "Cd") (pin "1") (pinfunction "1_1") (pintype "passive"))
      (node (ref "Cin1") (pin "2") (pinfunction "2_2") (pintype "passive"))
      (node (ref "Cin2") (pin "2") (pinfunction "2_2") (pintype "passive"))
      (node (ref "Cin3") (pin "2") (pinfunction "2_2") (pintype "passive"))
      (node (ref "Cin4") (pin "2") (pinfunction "2_2") (pintype "passive"))
      (node (ref "Cin5") (pin "2") (pinfunction "2_2") (pintype "passive"))
      (node (ref "Cin6") (pin "2") (pinfunction "2_2") (pintype "passive"))
      (node (ref "Cin7") (pin "2") (pinfunction "-_2") (pintype "passive"))
      (node (ref "Cin8") (pin "2") (pinfunction "2_2") (pintype "passive"))
      (node (ref "Co1") (pin "2") (pinfunction "2_2") (pintype "passive"))
      (node (ref "Co2") (pin "2") (pinfunction "2_2") (pintype "passive"))
      (node (ref "Co3") (pin "2") (pinfunction "2_2") (pintype "passive"))
      (node (ref "Co4") (pin "2") (pinfunction "2_2") (pintype "passive"))
      (node (ref "Co5") (pin "2") (pinfunction "2_2") (pintype "passive"))
      (node (ref "Co6") (pin "2") (pinfunction "2_2") (pintype "passive"))
      (node (ref "Co7") (pin "2") (pinfunction "-_2") (pintype "passive"))
      (node (ref "Css") (pin "2") (pinfunction "2_2") (pintype "passive"))
      (node (ref "Cvcc") (pin "2") (pinfunction "2_2") (pintype "passive"))
      (node (ref "J3") (pin "1") (pinfunction "1_1") (pintype "passive"))
      (node (ref "J4") (pin "1") (pinfunction "1_1") (pintype "passive"))
      (node (ref "R10") (pin "2") (pinfunction "2_2") (pintype "passive"))
      (node (ref "R14") (pin "2") (pinfunction "2_2") (pintype "passive"))
      (node (ref "R2") (pin "1") (pinfunction "1_1") (pintype "passive"))
      (node (ref "R8") (pin "1") (pinfunction "1_1") (pintype "passive"))
      (node (ref "RT1") (pin "1") (pinfunction "1_1") (pintype "passive"))
      (node (ref "Rs1") (pin "1") (pinfunction "1_1") (pintype "passive"))
      (node (ref "U1") (pin "10") (pinfunction "AGND_10") (pintype "power_in"))
      (node (ref "U1") (pin "13") (pinfunction "ISNS-_13") (pintype "input"))
      (node (ref "U1") (pin "14") (pinfunction "ISNS+_14") (pintype "input"))
      (node (ref "U1") (pin "22") (pinfunction "PGND_22") (pintype "power_in"))
      (node (ref "U1") (pin "29") (pinfunction "PAD_29") (pintype "power_in"))
    )
    (net (code "23") (name "Net-(C14-Pad2)") (class "Default")
      (node (ref "C14") (pin "2") (pinfunction "2_2") (pintype "passive"))
      (node (ref "SYNC") (pin "1") (pintype "passive"))
    )
    (net (code "24") (name "Net-(Cc1-Pad1)") (class "Default")
      (node (ref "Cc1") (pin "1") (pinfunction "1_1") (pintype "passive"))
      (node (ref "Rc") (pin "1") (pinfunction "1_1") (pintype "passive"))
    )
    (net (code "25") (name "Net-(D1-K)") (class "Default")
      (node (ref "D1") (pin "1") (pinfunction "K_1") (pintype "passive"))
      (node (ref "R5") (pin "2") (pinfunction "2_2") (pintype "passive"))
    )
    (net (code "26") (name "Net-(QH1-G)") (class "Default")
      (node (ref "QH1") (pin "4") (pinfunction "G_4") (pintype "passive"))
      (node (ref "Rh1") (pin "2") (pinfunction "2_2") (pintype "passive"))
    )
    (net (code "27") (name "Net-(QL1-S-Pad1)") (class "Default")
      (node (ref "QL1") (pin "1") (pinfunction "S_1") (pintype "passive"))
      (node (ref "QL1") (pin "2") (pinfunction "S_2") (pintype "passive"))
      (node (ref "QL1") (pin "3") (pinfunction "S_3") (pintype "passive"))
      (node (ref "QL2") (pin "1") (pinfunction "S_1") (pintype "passive"))
      (node (ref "QL2") (pin "2") (pinfunction "S_2") (pintype "passive"))
      (node (ref "QL2") (pin "3") (pinfunction "S_3") (pintype "passive"))
      (node (ref "R13") (pin "2") (pinfunction "2_2") (pintype "passive"))
      (node (ref "Rs1") (pin "2") (pinfunction "2_2") (pintype "passive"))
    )
    (net (code "28") (name "Net-(QL2-G)") (class "Default")
      (node (ref "QL2") (pin "4") (pinfunction "G_4") (pintype "passive"))
      (node (ref "Rl1") (pin "1") (pinfunction "1_1") (pintype "passive"))
    )
    (net (code "29") (name "Net-(R12-Pad1)") (class "Default")
      (node (ref "R12") (pin "1") (pinfunction "1_1") (pintype "passive"))
      (node (ref "R16") (pin "2") (pinfunction "2_2") (pintype "passive"))
    )
    (net (code "30") (name "Net-(R15-Pad1)") (class "Default")
      (node (ref "R15") (pin "1") (pinfunction "1_1") (pintype "passive"))
      (node (ref "TRIM") (pin "1") (pintype "passive"))
    )
    (net (code "31") (name "Net-(U1-CS)") (class "Default")
      (node (ref "C13") (pin "2") (pinfunction "2_2") (pintype "passive"))
      (node (ref "R13") (pin "1") (pinfunction "1_1") (pintype "passive"))
      (node (ref "U1") (pin "16") (pinfunction "CS_16") (pintype "input"))
    )
    (net (code "32") (name "Net-(U1-CSG)") (class "Default")
      (node (ref "C13") (pin "1") (pinfunction "1_1") (pintype "passive"))
      (node (ref "R14") (pin "1") (pinfunction "1_1") (pintype "passive"))
      (node (ref "U1") (pin "15") (pinfunction "CSG_15") (pintype "input"))
    )
    (net (code "33") (name "VCC") (class "Default")
      (node (ref "Cvcc") (pin "1") (pinfunction "1_1") (pintype "passive"))
      (node (ref "D2") (pin "2") (pinfunction "A_2") (pintype "passive"))
      (node (ref "D3") (pin "2") (pinfunction "A_2") (pintype "passive"))
      (node (ref "R7") (pin "2") (pinfunction "2_2") (pintype "passive"))
      (node (ref "Rpg") (pin "1") (pinfunction "1_1") (pintype "passive"))
      (node (ref "U1") (pin "23") (pinfunction "VCC_23") (pintype "power_in"))
    )
    (net (code "34") (name "VIN") (class "Default")
      (node (ref "Cin1") (pin "1") (pinfunction "1_1") (pintype "passive"))
      (node (ref "Cin2") (pin "1") (pinfunction "1_1") (pintype "passive"))
      (node (ref "Cin3") (pin "1") (pinfunction "1_1") (pintype "passive"))
      (node (ref "Cin4") (pin "1") (pinfunction "1_1") (pintype "passive"))
      (node (ref "Cin5") (pin "1") (pinfunction "1_1") (pintype "passive"))
      (node (ref "Cin6") (pin "1") (pinfunction "1_1") (pintype "passive"))
      (node (ref "Cin7") (pin "1") (pinfunction "+_1") (pintype "passive"))
      (node (ref "D1") (pin "2") (pinfunction "A_2") (pintype "passive"))
      (node (ref "J1") (pin "1") (pinfunction "1_1") (pintype "passive"))
      (node (ref "QH1") (pin "5") (pinfunction "D_5") (pintype "passive"))
      (node (ref "QH1") (pin "6") (pinfunction "D_6") (pintype "passive"))
      (node (ref "QH1") (pin "7") (pinfunction "D_7") (pintype "passive"))
      (node (ref "QH1") (pin "8") (pinfunction "D_8") (pintype "passive"))
      (node (ref "QH1") (pin "9") (pinfunction "D_9") (pintype "passive"))
      (node (ref "R1") (pin "2") (pinfunction "2_2") (pintype "passive"))
      (node (ref "R6") (pin "1") (pinfunction "1_1") (pintype "passive"))
    )
    (net (code "35") (name "VOUT") (class "Default")
      (node (ref "Co1") (pin "1") (pinfunction "1_1") (pintype "passive"))
      (node (ref "Co2") (pin "1") (pinfunction "1_1") (pintype "passive"))
      (node (ref "Co3") (pin "1") (pinfunction "1_1") (pintype "passive"))
      (node (ref "Co4") (pin "1") (pinfunction "1_1") (pintype "passive"))
      (node (ref "Co5") (pin "1") (pinfunction "1_1") (pintype "passive"))
      (node (ref "Co6") (pin "1") (pinfunction "1_1") (pintype "passive"))
      (node (ref "Co7") (pin "1") (pinfunction "+_1") (pintype "passive"))
      (node (ref "J2") (pin "1") (pinfunction "1_1") (pintype "passive"))
      (node (ref "QH2") (pin "5") (pinfunction "D_5") (pintype "passive"))
      (node (ref "QH2") (pin "6") (pinfunction "D_6") (pintype "passive"))
      (node (ref "QH2") (pin "7") (pinfunction "D_7") (pintype "passive"))
      (node (ref "QH2") (pin "8") (pinfunction "D_8") (pintype "passive"))
      (node (ref "QH2") (pin "9") (pinfunction "D_9") (pintype "passive"))
      (node (ref "R16") (pin "1") (pinfunction "1_1") (pintype "passive"))
      (node (ref "R3") (pin "2") (pinfunction "2_2") (pintype "passive"))
      (node (ref "R4") (pin "2") (pinfunction "2_2") (pintype "passive"))
    )
  )
)
